# Accelerometer_-_MMA8452Q.net
KiCad netlist of a schematic drawn in EAGLE
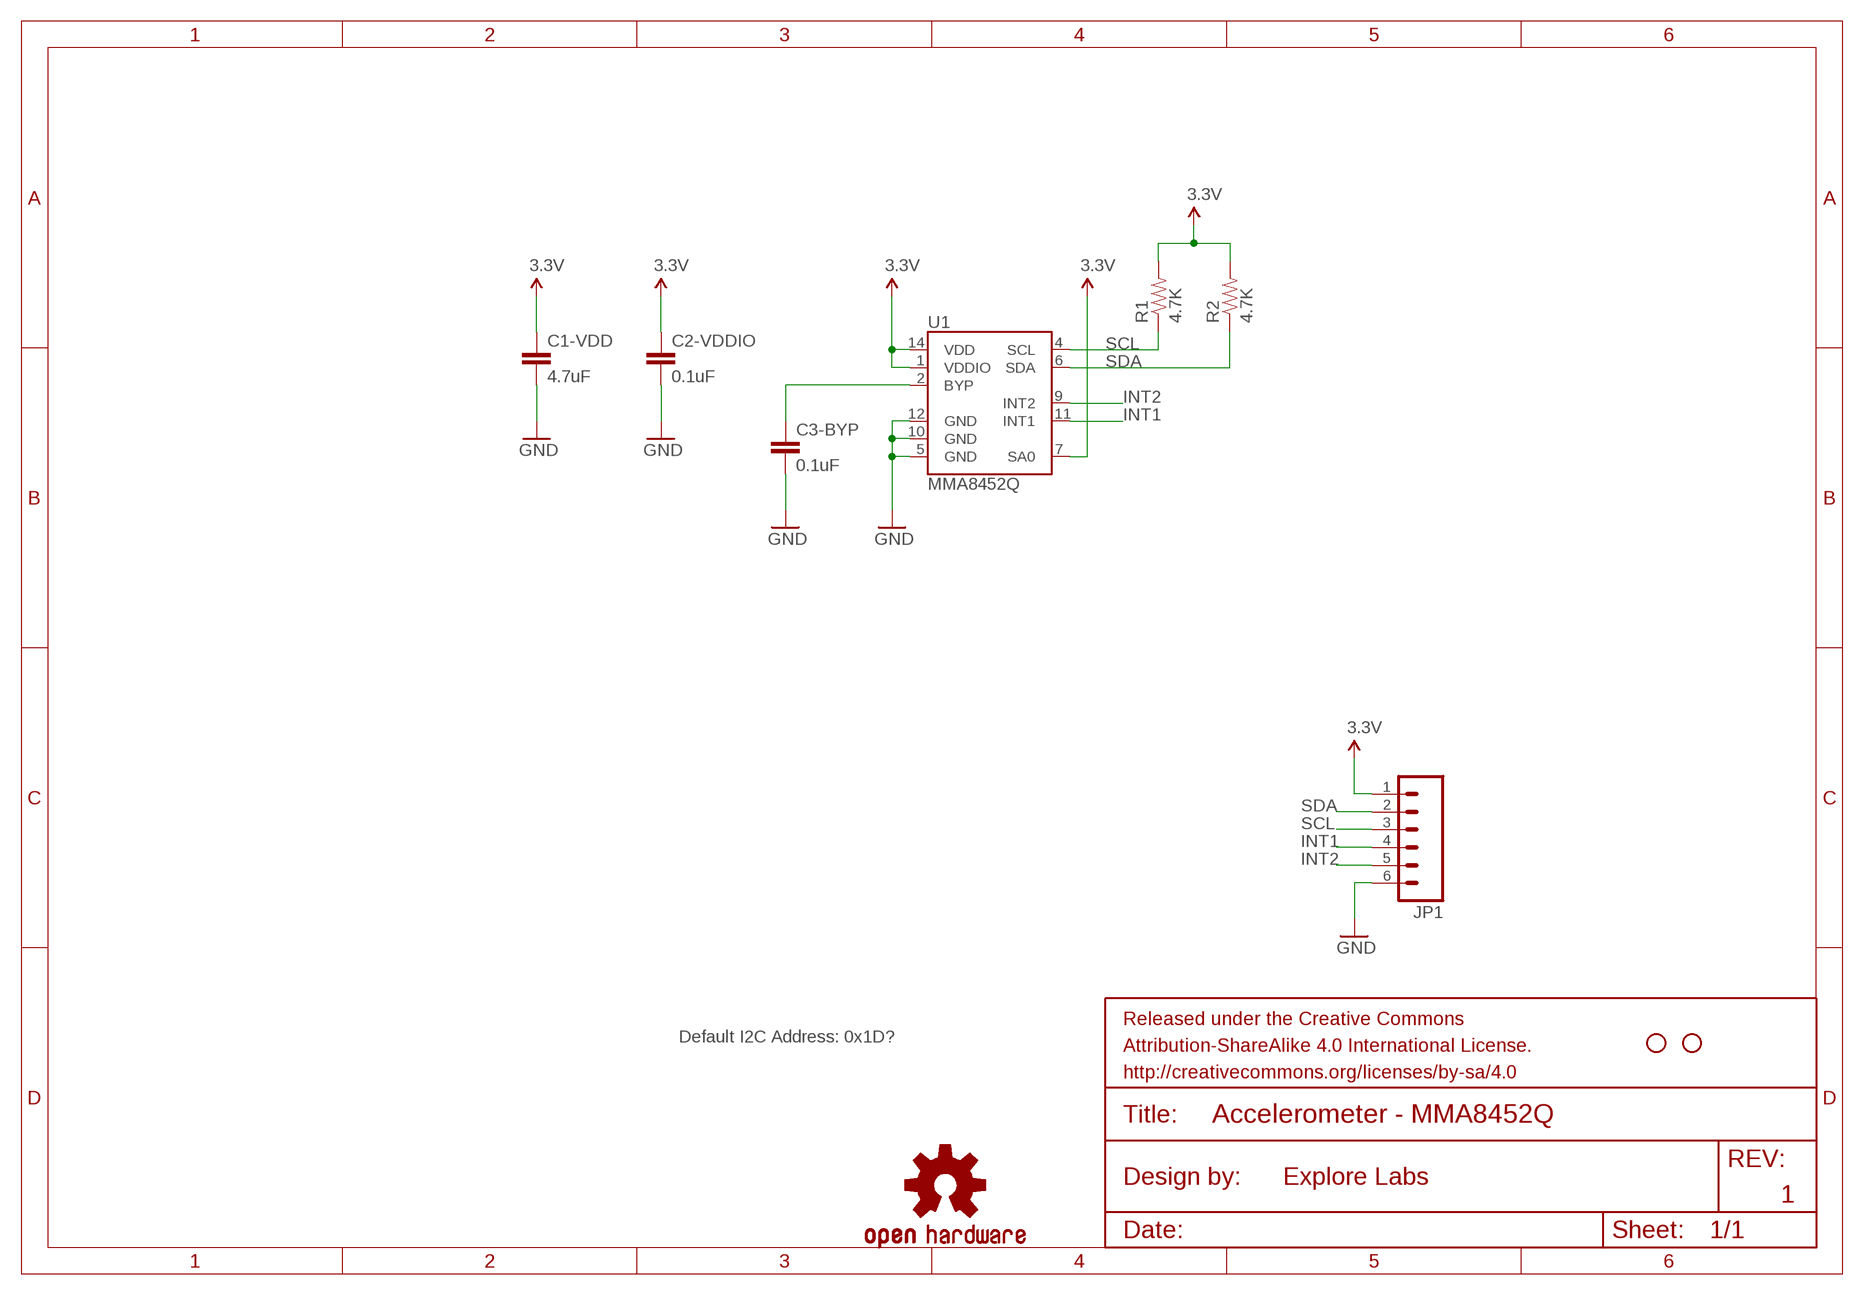
[diagram p0: schematic, sheet 1]

(export (version "E")
  (design (tool "Eeschema 10.0.6"))
  (components
    (comp (ref "C1-VDD")
      (value "4.7uF")
      (footprint "eagle-import:0603-CAP")
      (libsource (lib "eagle-import") (part "CAP0603-CAP"))
    )
    (comp (ref "C2-VDDIO")
      (value "0.1uF")
      (footprint "eagle-import:0603-CAP")
      (libsource (lib "eagle-import") (part "CAP0603-CAP"))
    )
    (comp (ref "C3-BYP")
      (value "0.1uF")
      (footprint "eagle-import:0603-CAP")
      (libsource (lib "eagle-import") (part "CAP0603-CAP"))
    )
    (comp (ref "JP1")
      (value "M06SILK_FEMALE_PTH")
      (footprint "eagle-import:1X06")
      (libsource (lib "eagle-import") (part "M06SILK_FEMALE_PTH"))
    )
    (comp (ref "LOGO1")
      (value "OSHW-LOGOS")
      (footprint "eagle-import:OSHW-LOGO-S")
      (libsource (lib "eagle-import") (part "OSHW-LOGOS"))
    )
    (comp (ref "R1")
      (value "4.7K")
      (footprint "eagle-import:0603-RES")
      (libsource (lib "eagle-import") (part "RESISTOR0603-RES"))
    )
    (comp (ref "R2")
      (value "4.7K")
      (footprint "eagle-import:0603-RES")
      (libsource (lib "eagle-import") (part "RESISTOR0603-RES"))
    )
    (comp (ref "STANDOFF1")
      (value "STAND-OFFTIGHT")
      (footprint "eagle-import:STAND-OFF-TIGHT")
      (libsource (lib "eagle-import") (part "STAND-OFFTIGHT"))
    )
    (comp (ref "STANDOFF2")
      (value "STAND-OFFTIGHT")
      (footprint "eagle-import:STAND-OFF-TIGHT")
      (libsource (lib "eagle-import") (part "STAND-OFFTIGHT"))
    )
    (comp (ref "U1")
      (value "MMA8452Q")
      (footprint "eagle-import:QFN-16_0.5MM")
      (libsource (lib "eagle-import") (part "MMA8452Q"))
    )
  )
  (nets
    (net (code "1") (name "/INT1") (class "Default")
      (node (ref "JP1") (pin "4") (pinfunction "4_4") (pintype "passive"))
      (node (ref "U1") (pin "11") (pinfunction "INT1_11") (pintype "bidirectional"))
    )
    (net (code "2") (name "/INT2") (class "Default")
      (node (ref "JP1") (pin "5") (pinfunction "5_5") (pintype "passive"))
      (node (ref "U1") (pin "9") (pinfunction "INT2_9") (pintype "bidirectional"))
    )
    (net (code "3") (name "/SCL") (class "Default")
      (node (ref "JP1") (pin "3") (pinfunction "3_3") (pintype "passive"))
      (node (ref "R1") (pin "1") (pinfunction "1_1") (pintype "passive"))
      (node (ref "U1") (pin "4") (pinfunction "SCL_4") (pintype "bidirectional"))
    )
    (net (code "4") (name "/SDA") (class "Default")
      (node (ref "JP1") (pin "2") (pinfunction "2_2") (pintype "passive"))
      (node (ref "R2") (pin "1") (pinfunction "1_1") (pintype "passive"))
      (node (ref "U1") (pin "6") (pinfunction "SDA_6") (pintype "bidirectional"))
    )
    (net (code "5") (name "3.3V") (class "Default")
      (node (ref "C1-VDD") (pin "1") (pinfunction "1_1") (pintype "passive"))
      (node (ref "C2-VDDIO") (pin "1") (pinfunction "1_1") (pintype "passive"))
      (node (ref "JP1") (pin "1") (pinfunction "1_1") (pintype "passive"))
      (node (ref "R1") (pin "2") (pinfunction "2_2") (pintype "passive"))
      (node (ref "R2") (pin "2") (pinfunction "2_2") (pintype "passive"))
      (node (ref "U1") (pin "1") (pinfunction "VDDIO_1") (pintype "bidirectional"))
      (node (ref "U1") (pin "14") (pinfunction "VDD_14") (pintype "bidirectional"))
      (node (ref "U1") (pin "7") (pinfunction "SA0_7") (pintype "bidirectional"))
    )
    (net (code "6") (name "GND") (class "Default")
      (node (ref "C1-VDD") (pin "2") (pinfunction "2_2") (pintype "passive"))
      (node (ref "C2-VDDIO") (pin "2") (pinfunction "2_2") (pintype "passive"))
      (node (ref "C3-BYP") (pin "2") (pinfunction "2_2") (pintype "passive"))
      (node (ref "JP1") (pin "6") (pinfunction "6_6") (pintype "passive"))
      (node (ref "U1") (pin "10") (pinfunction "GND_10") (pintype "bidirectional"))
      (node (ref "U1") (pin "12") (pinfunction "GND_12") (pintype "bidirectional"))
      (node (ref "U1") (pin "5") (pinfunction "GND_5") (pintype "bidirectional"))
    )
    (net (code "7") (name "Net-(U1-BYP)") (class "Default")
      (node (ref "C3-BYP") (pin "1") (pinfunction "1_1") (pintype "passive"))
      (node (ref "U1") (pin "2") (pinfunction "BYP_2") (pintype "bidirectional"))
    )
  )
)
